# LB11920.net
KiCad netlist of a schematic drawn in Altium Designer
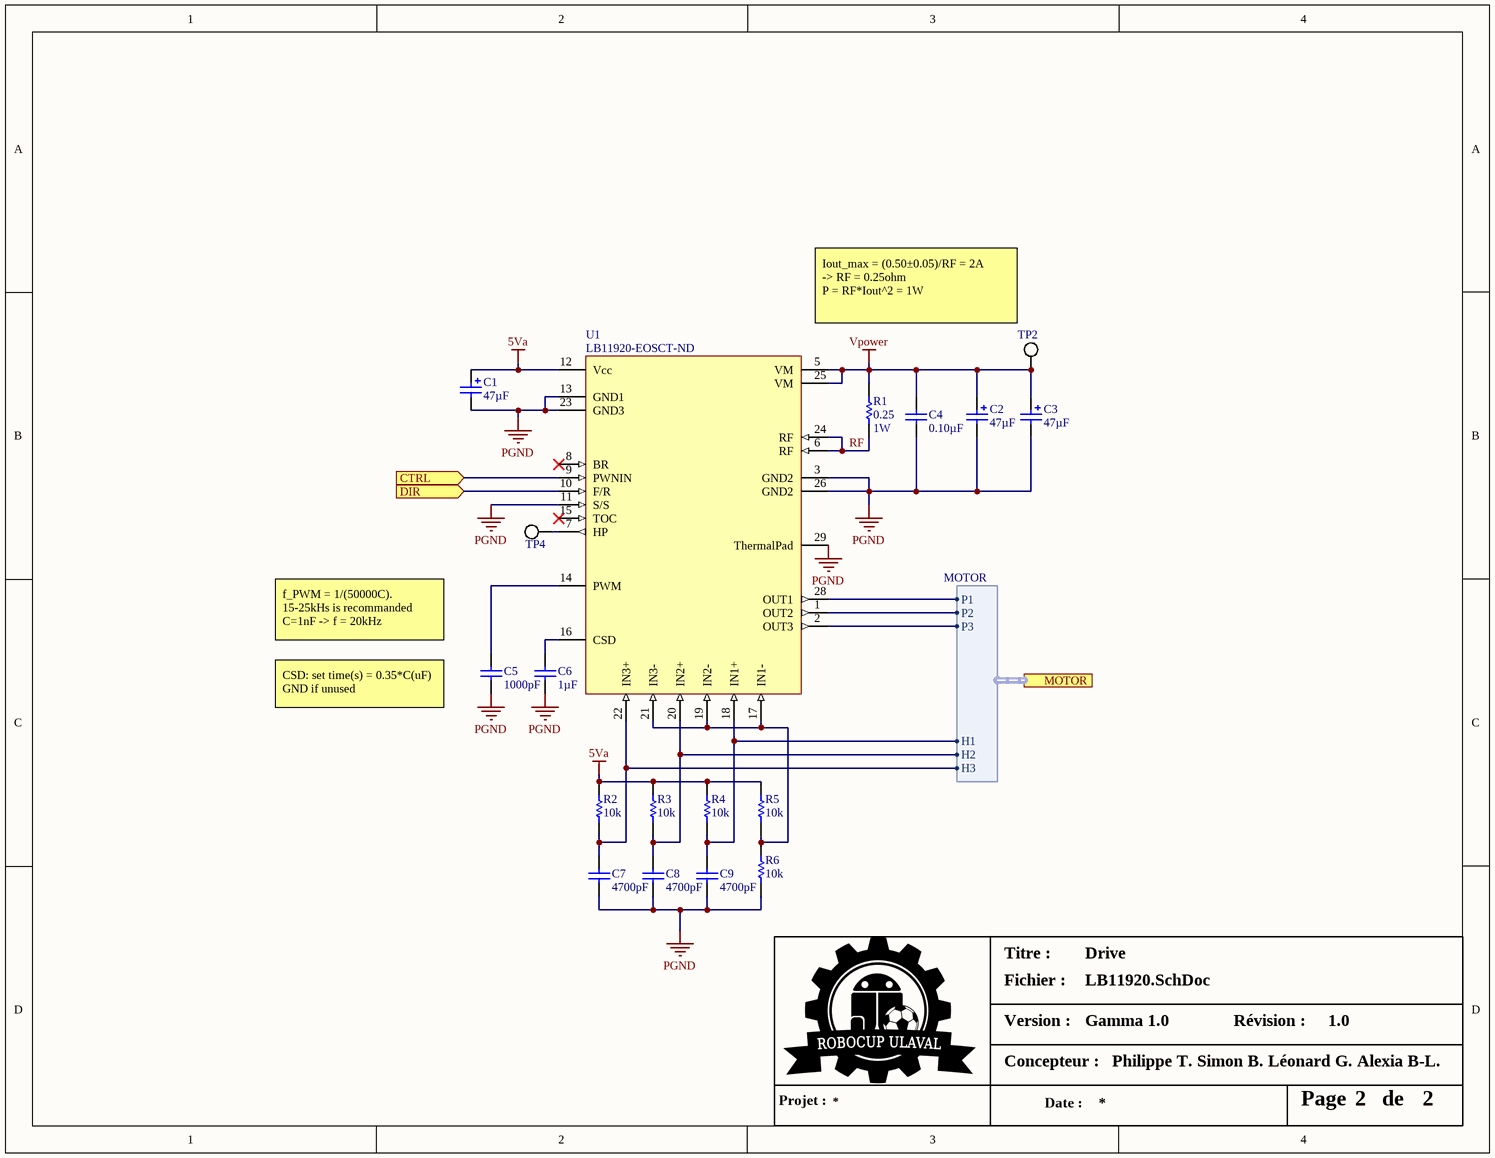
[diagram p0: LB11920.SchDoc]

(export (version "E")
  (design (tool "Eeschema 10.0.6"))
  (components
    (comp (ref "C1")
      (value "865080645012")
      (footprint "CAP 6.6x6.6mm")
      (description "CAP 47 UF 20% 50 V")
      (fields
        (field (name "MANUFACTURER") "Wurth Electronics Inc")
        (field (name "TOLERANCE") "±20%")
        (field (name "CAPACITANCE") "47µF")
      )
      (libsource (lib "ResCap") (part "865080645012"))
    )
    (comp (ref "C2")
      (value "865080645012")
      (footprint "CAP 6.6x6.6mm")
      (description "CAP 47 UF 20% 50 V")
      (fields
        (field (name "MANUFACTURER") "Wurth Electronics Inc")
        (field (name "TOLERANCE") "±20%")
        (field (name "CAPACITANCE") "47µF")
      )
      (libsource (lib "ResCap") (part "865080645012"))
    )
    (comp (ref "C3")
      (value "865080645012")
      (footprint "CAP 6.6x6.6mm")
      (description "CAP 47 UF 20% 50 V")
      (fields
        (field (name "MANUFACTURER") "Wurth Electronics Inc")
        (field (name "TOLERANCE") "±20%")
        (field (name "CAPACITANCE") "47µF")
      )
      (libsource (lib "ResCap") (part "865080645012"))
    )
    (comp (ref "C4")
      (value "CL10B104KB8SFNC")
      (footprint "0603")
      (description "CAP CER 0.1UF 50V X7R 0603")
      (fields
        (field (name "MANUFACTURER") "Samsung Electro-Mechanics America, Inc.")
        (field (name "TOLERANCE") "±10%")
        (field (name "CAPACITANCE") "0.10µF")
      )
      (libsource (lib "ResCap") (part "CL10B104KB8SFNC"))
    )
    (comp (ref "C5")
      (value "CL10B102KB8NNNC")
      (footprint "0603")
      (description "CAP CER 1000PF 50V X7R 0603")
      (fields
        (field (name "MANUFACTURER") "Samsung Electro-Mechanics America, Inc.")
        (field (name "TOLERANCE") "±10%")
        (field (name "CAPACITANCE") "1000pF")
      )
      (libsource (lib "ResCap") (part "CL10B102KB8NNNC"))
    )
    (comp (ref "C6")
      (value "CL21B105KBFNFNE")
      (footprint "0805")
      (description "CAP CER 1UF 50V X7R 0805")
      (fields
        (field (name "MANUFACTURER") "Samsung Electro-Mechanics America, Inc.")
        (field (name "TOLERANCE") "±10%")
        (field (name "CAPACITANCE") "1µF")
      )
      (libsource (lib "ResCap") (part "CL21B105KBFNFNE"))
    )
    (comp (ref "C7")
      (value "CL10B472KB8NNNC")
      (footprint "0603")
      (description "CAP CER 4700PF 50V X7R 0603")
      (fields
        (field (name "MANUFACTURER") "Samsung Electro-Mechanics America, Inc.")
        (field (name "TOLERANCE") "±10%")
        (field (name "CAPACITANCE") "4700pF")
      )
      (libsource (lib "ResCap") (part "CL10B472KB8NNNC"))
    )
    (comp (ref "C8")
      (value "CL10B472KB8NNNC")
      (footprint "0603")
      (description "CAP CER 4700PF 50V X7R 0603")
      (fields
        (field (name "MANUFACTURER") "Samsung Electro-Mechanics America, Inc.")
        (field (name "TOLERANCE") "±10%")
        (field (name "CAPACITANCE") "4700pF")
      )
      (libsource (lib "ResCap") (part "CL10B472KB8NNNC"))
    )
    (comp (ref "C9")
      (value "CL10B472KB8NNNC")
      (footprint "0603")
      (description "CAP CER 4700PF 50V X7R 0603")
      (fields
        (field (name "MANUFACTURER") "Samsung Electro-Mechanics America, Inc.")
        (field (name "TOLERANCE") "±10%")
        (field (name "CAPACITANCE") "4700pF")
      )
      (libsource (lib "ResCap") (part "CL10B472KB8NNNC"))
    )
    (comp (ref "R1")
      (value "CSRN2010FKR250")
      (footprint "2010")
      (description "RES SMD 0.25 OHM 1% 1W 2010")
      (fields
        (field (name "MANUFACTURER") "Stackpole Electronics Inc.")
        (field (name "TOLERANCE") "±1%")
        (field (name "RESISTANCE (OHMS)") "0.25")
        (field (name "POWER (WATTS)") "1W")
      )
      (libsource (lib "ResCap") (part "CSRN2010FKR250"))
    )
    (comp (ref "R2")
      (value "RC0603JR-0710KL")
      (footprint "0603")
      (description "RES SMD 10K OHM 5% 1/10W 0603")
      (fields
        (field (name "MANUFACTURER") "Yageo")
        (field (name "TOLERANCE") "±5%")
        (field (name "RESISTANCE (OHMS)") "10k")
      )
      (libsource (lib "ResCap") (part "RC0603JR-0710KL"))
    )
    (comp (ref "R3")
      (value "RC0603JR-0710KL")
      (footprint "0603")
      (description "RES SMD 10K OHM 5% 1/10W 0603")
      (fields
        (field (name "MANUFACTURER") "Yageo")
        (field (name "TOLERANCE") "±5%")
        (field (name "RESISTANCE (OHMS)") "10k")
      )
      (libsource (lib "ResCap") (part "RC0603JR-0710KL"))
    )
    (comp (ref "R4")
      (value "RC0603JR-0710KL")
      (footprint "0603")
      (description "RES SMD 10K OHM 5% 1/10W 0603")
      (fields
        (field (name "MANUFACTURER") "Yageo")
        (field (name "TOLERANCE") "±5%")
        (field (name "RESISTANCE (OHMS)") "10k")
      )
      (libsource (lib "ResCap") (part "RC0603JR-0710KL"))
    )
    (comp (ref "R5")
      (value "RC0603JR-0710KL")
      (footprint "0603")
      (description "RES SMD 10K OHM 5% 1/10W 0603")
      (fields
        (field (name "MANUFACTURER") "Yageo")
        (field (name "TOLERANCE") "±5%")
        (field (name "RESISTANCE (OHMS)") "10k")
      )
      (libsource (lib "ResCap") (part "RC0603JR-0710KL"))
    )
    (comp (ref "R6")
      (value "RC0603JR-0710KL")
      (footprint "0603")
      (description "RES SMD 10K OHM 5% 1/10W 0603")
      (fields
        (field (name "MANUFACTURER") "Yageo")
        (field (name "TOLERANCE") "±5%")
        (field (name "RESISTANCE (OHMS)") "10k")
      )
      (libsource (lib "ResCap") (part "RC0603JR-0710KL"))
    )
    (comp (ref "TP2")
      (value "testpoint")
      (footprint "0805 testpoint")
      (description "Testpoint")
      (libsource (lib "BrushlessDrive") (part "testpoint"))
    )
    (comp (ref "TP4")
      (value "testpoint")
      (footprint "0805 testpoint")
      (description "Testpoint")
      (libsource (lib "BrushlessDrive") (part "testpoint"))
    )
    (comp (ref "U1")
      (value "LB11920-E")
      (footprint "DIP28")
      (description "IC MOTOR DRIVER PAR 28HDIP")
      (fields
        (field (name "MANUFACTURER") "ON Semiconductor")
        (field (name "SUPPLIER PART NUMBER 1") "LB11920-EOSCT-ND")
      )
      (libsource (lib "BrushlessDrive") (part "LB11920-E"))
    )
  )
  (nets
    (net (code "2") (name "/CTRL") (class "Default")
      (node (ref "U1") (pin "9") (pinfunction "PWNIN_9") (pintype "input"))
    )
    (net (code "3") (name "/DIR") (class "Default")
      (node (ref "U1") (pin "10") (pinfunction "F/R_10") (pintype "input"))
    )
    (net (code "4") (name "/H1") (class "Default")
      (node (ref "C9") (pin "2") (pinfunction "2_2") (pintype "passive"))
      (node (ref "R4") (pin "1") (pinfunction "1_1") (pintype "passive"))
      (node (ref "U1") (pin "18") (pinfunction "IN1+_18") (pintype "input"))
    )
    (net (code "5") (name "/H2") (class "Default")
      (node (ref "C8") (pin "2") (pinfunction "2_2") (pintype "passive"))
      (node (ref "R3") (pin "1") (pinfunction "1_1") (pintype "passive"))
      (node (ref "U1") (pin "20") (pinfunction "IN2+_20") (pintype "input"))
    )
    (net (code "6") (name "/H3") (class "Default")
      (node (ref "C7") (pin "2") (pinfunction "2_2") (pintype "passive"))
      (node (ref "R2") (pin "1") (pinfunction "1_1") (pintype "passive"))
      (node (ref "U1") (pin "22") (pinfunction "IN3+_22") (pintype "input"))
    )
    (net (code "7") (name "/P1") (class "Default")
      (node (ref "U1") (pin "28") (pinfunction "OUT1_28") (pintype "output"))
    )
    (net (code "8") (name "/P2") (class "Default")
      (node (ref "U1") (pin "1") (pinfunction "OUT2_1") (pintype "output"))
    )
    (net (code "9") (name "/P3") (class "Default")
      (node (ref "U1") (pin "2") (pinfunction "OUT3_2") (pintype "output"))
    )
    (net (code "10") (name "/RF") (class "Default")
      (node (ref "R1") (pin "1") (pinfunction "1_1") (pintype "passive"))
      (node (ref "U1") (pin "24") (pinfunction "RF_24") (pintype "input"))
      (node (ref "U1") (pin "6") (pinfunction "RF_6") (pintype "input"))
    )
    (net (code "12") (name "5Va") (class "Default")
      (node (ref "C1") (pin "1") (pinfunction "1_1") (pintype "passive"))
      (node (ref "R2") (pin "2") (pinfunction "2_2") (pintype "passive"))
      (node (ref "R3") (pin "2") (pinfunction "2_2") (pintype "passive"))
      (node (ref "R4") (pin "2") (pinfunction "2_2") (pintype "passive"))
      (node (ref "R5") (pin "2") (pinfunction "2_2") (pintype "passive"))
      (node (ref "U1") (pin "12") (pinfunction "Vcc_12") (pintype "power_in"))
    )
    (net (code "13") (name "Net-(U1-CSD)") (class "Default")
      (node (ref "C6") (pin "2") (pinfunction "2_2") (pintype "passive"))
      (node (ref "U1") (pin "16") (pinfunction "CSD_16") (pintype "passive"))
    )
    (net (code "14") (name "Net-(U1-HP)") (class "Default")
      (node (ref "TP4") (pin "1") (pinfunction "1_1") (pintype "passive"))
      (node (ref "U1") (pin "7") (pinfunction "HP_7") (pintype "output"))
    )
    (net (code "15") (name "Net-(U1-IN1-)") (class "Default")
      (node (ref "R5") (pin "1") (pinfunction "1_1") (pintype "passive"))
      (node (ref "R6") (pin "2") (pinfunction "2_2") (pintype "passive"))
      (node (ref "U1") (pin "17") (pinfunction "IN1-_17") (pintype "input"))
      (node (ref "U1") (pin "19") (pinfunction "IN2-_19") (pintype "input"))
      (node (ref "U1") (pin "21") (pinfunction "IN3-_21") (pintype "input"))
    )
    (net (code "16") (name "Net-(U1-PWM)") (class "Default")
      (node (ref "C5") (pin "2") (pinfunction "2_2") (pintype "passive"))
      (node (ref "U1") (pin "14") (pinfunction "PWM_14") (pintype "passive"))
    )
    (net (code "17") (name "PGND") (class "Default")
      (node (ref "C1") (pin "2") (pinfunction "2_2") (pintype "passive"))
      (node (ref "C2") (pin "2") (pinfunction "2_2") (pintype "passive"))
      (node (ref "C3") (pin "2") (pinfunction "2_2") (pintype "passive"))
      (node (ref "C4") (pin "1") (pinfunction "1_1") (pintype "passive"))
      (node (ref "C5") (pin "1") (pinfunction "1_1") (pintype "passive"))
      (node (ref "C6") (pin "1") (pinfunction "1_1") (pintype "passive"))
      (node (ref "C7") (pin "1") (pinfunction "1_1") (pintype "passive"))
      (node (ref "C8") (pin "1") (pinfunction "1_1") (pintype "passive"))
      (node (ref "C9") (pin "1") (pinfunction "1_1") (pintype "passive"))
      (node (ref "R6") (pin "1") (pinfunction "1_1") (pintype "passive"))
      (node (ref "U1") (pin "11") (pinfunction "S/S_11") (pintype "input"))
      (node (ref "U1") (pin "13") (pinfunction "GND1_13") (pintype "power_in"))
      (node (ref "U1") (pin "23") (pinfunction "GND3_23") (pintype "power_in"))
      (node (ref "U1") (pin "26") (pinfunction "GND2_26") (pintype "power_in"))
      (node (ref "U1") (pin "29") (pinfunction "ThermalPad_29") (pintype "power_in"))
      (node (ref "U1") (pin "3") (pinfunction "GND2_3") (pintype "power_in"))
    )
    (net (code "18") (name "Vpower") (class "Default")
      (node (ref "C2") (pin "1") (pinfunction "1_1") (pintype "passive"))
      (node (ref "C3") (pin "1") (pinfunction "1_1") (pintype "passive"))
      (node (ref "C4") (pin "2") (pinfunction "2_2") (pintype "passive"))
      (node (ref "R1") (pin "2") (pinfunction "2_2") (pintype "passive"))
      (node (ref "TP2") (pin "1") (pinfunction "1_1") (pintype "passive"))
      (node (ref "U1") (pin "25") (pinfunction "VM_25") (pintype "power_in"))
      (node (ref "U1") (pin "5") (pinfunction "VM_5") (pintype "power_in"))
    )
    (net (code "19") (name "unconnected-(U1-BR-Pad8)") (class "Default")
      (node (ref "U1") (pin "8") (pinfunction "BR_8") (pintype "input+no_connect"))
    )
    (net (code "20") (name "unconnected-(U1-TOC-Pad15)") (class "Default")
      (node (ref "U1") (pin "15") (pinfunction "TOC_15") (pintype "input+no_connect"))
    )
  )
)
